# Power.net
KiCad netlist of a schematic drawn in Altium Designer
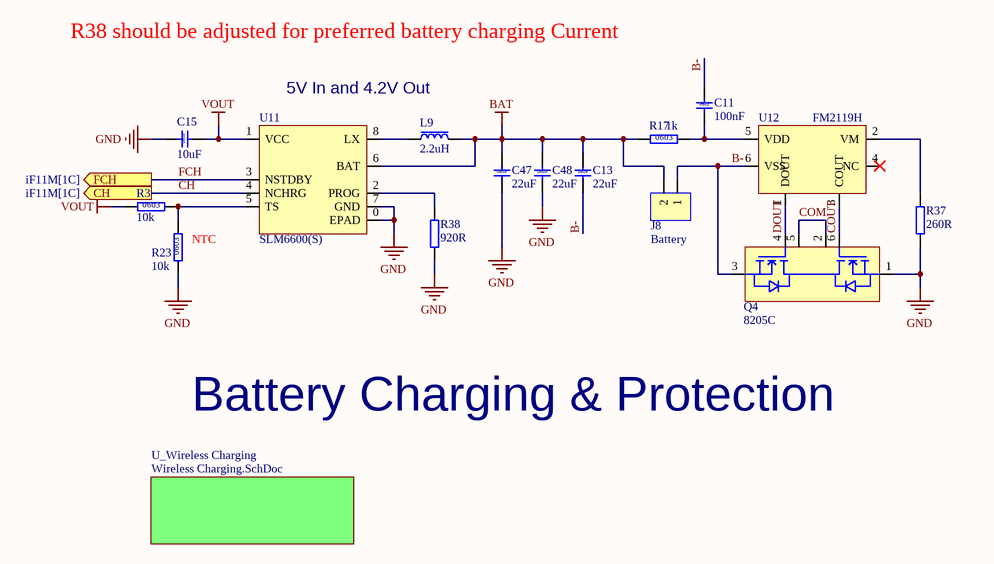
[diagram p0: Power.SchDoc]

(export (version "E")
  (design (tool "Eeschema 10.0.6"))
  (components
    (comp (ref "C11")
      (value "100nF")
      (footprint "C0603")
      (description "10% 50V")
      (fields (field (name "PART NO") "W-T-CA-X703N100K50VNT") (field (name "MANUFACTURER") "FENGHUA"))
      (libsource (lib "Rescap") (part "C 0603 100nF 50V"))
    )
    (comp (ref "C13")
      (value "22uF")
      (footprint "C0805")
      (description "10% 16V")
      (fields (field (name "PART NO") "WP0005367"))
      (libsource (lib "Rescap") (part "C 0805 22uF 16V"))
    )
    (comp (ref "C15")
      (value "10uF")
      (footprint "C0805")
      (description "10% 25V")
      (fields (field (name "PART NO") "WP0005368"))
      (libsource (lib "Rescap") (part "C 0805 10uF 25V"))
    )
    (comp (ref "C47")
      (value "22uF")
      (footprint "C0805")
      (description "10% 16V")
      (fields (field (name "PART NO") "WP0005367"))
      (libsource (lib "Rescap") (part "C 0805 22uF 16V"))
    )
    (comp (ref "C48")
      (value "22uF")
      (footprint "C0805")
      (description "10% 16V")
      (fields (field (name "PART NO") "WP0005367"))
      (libsource (lib "Rescap") (part "C 0805 22uF 16V"))
    )
    (comp (ref "J8")
      (value "Battery")
      (footprint "B2B-PH-2mm")
      (description "B2B PH 1X2 2 Pin B2B Connector")
      (libsource (lib "Connector") (part "B2B-PH-2MM"))
    )
    (comp (ref "L9")
      (value "2.2uH")
      (footprint "CD54")
      (description "SMD Inductor 2.2 uH CD54")
      (libsource (lib "Inductor") (part "CD54"))
    )
    (comp (ref "Q4")
      (value "8205C")
      (footprint "SOT23-6")
      (description "20V N-channel enhancement MOS field effect transistor")
      (libsource (lib "Transistor") (part "JST8205S"))
    )
    (comp (ref "R3")
      (value "10k")
      (footprint "R0603-LD")
      (description "5%")
      (fields (field (name "PART NO") "W-T-RE-RS03K103JT") (field (name "MANUFACTURER") "热敏D541V11增加1颗用量"))
      (libsource (lib "Rescap") (part "R 0603 10k"))
    )
    (comp (ref "R17")
      (value "1k")
      (footprint "R0603-LD")
      (description "5%")
      (fields (field (name "PART NO") "W-T-RE-RS03K102JT") (field (name "MANUFACTURER") "LAGEO"))
      (libsource (lib "Rescap") (part "R 0603 1k"))
    )
    (comp (ref "R23")
      (value "10k")
      (footprint "R0603-LD")
      (description "5%")
      (fields (field (name "PART NO") "W-T-RE-RS03K103JT") (field (name "MANUFACTURER") "热敏D541V11增加1颗用量"))
      (libsource (lib "Rescap") (part "R 0603 10k"))
    )
    (comp (ref "R37") (value "260R") (footprint "R0603") (libsource (lib "Resistor") (part "Resistor")))
    (comp (ref "R38") (value "920R") (footprint "R0603") (libsource (lib "Resistor") (part "Resistor")))
    (comp (ref "U11")
      (value "SLM6600(S)")
      (footprint "SOP-8 - EPAD")
      (libsource (lib "mylib2") (part "SLM6600(S)"))
    )
    (comp (ref "U12") (value "FM2119H") (footprint "SOT23-6") (libsource (lib "mylib2") (part "FM2119H")))
  )
  (nets
    (net (code "1") (name "/B-") (class "Default")
      (node (ref "C11") (pin "1") (pinfunction "1_1") (pintype "passive"))
      (node (ref "C13") (pin "2") (pinfunction "2_2") (pintype "passive"))
      (node (ref "J8") (pin "1") (pinfunction "1_1") (pintype "passive"))
      (node (ref "Q4") (pin "3") (pinfunction "S2_3") (pintype "passive"))
      (node (ref "U12") (pin "6") (pinfunction "VSS_6") (pintype "passive"))
    )
    (net (code "2") (name "/CH") (class "Default")
      (node (ref "U11") (pin "4") (pinfunction "NCHRG_4") (pintype "passive"))
    )
    (net (code "3") (name "/COM") (class "Default")
      (node (ref "Q4") (pin "2") (pinfunction "D1_2") (pintype "passive"))
      (node (ref "Q4") (pin "5") (pinfunction "D2_5") (pintype "passive"))
    )
    (net (code "4") (name "/COUT") (class "Default")
      (node (ref "Q4") (pin "6") (pinfunction "G1_6") (pintype "passive"))
      (node (ref "U12") (pin "3") (pinfunction "COUT_3") (pintype "passive"))
    )
    (net (code "5") (name "/DOUT") (class "Default")
      (node (ref "Q4") (pin "4") (pinfunction "G2_4") (pintype "passive"))
      (node (ref "U12") (pin "1") (pinfunction "DOUT_1") (pintype "passive"))
    )
    (net (code "6") (name "/FCH") (class "Default")
      (node (ref "U11") (pin "3") (pinfunction "NSTDBY_3") (pintype "passive"))
    )
    (net (code "7") (name "BAT") (class "Default")
      (node (ref "C13") (pin "1") (pinfunction "1_1") (pintype "passive"))
      (node (ref "C47") (pin "1") (pinfunction "1_1") (pintype "passive"))
      (node (ref "C48") (pin "1") (pinfunction "1_1") (pintype "passive"))
      (node (ref "J8") (pin "2") (pinfunction "2_2") (pintype "passive"))
      (node (ref "L9") (pin "2") (pinfunction "2_2") (pintype "passive"))
      (node (ref "R17") (pin "1") (pinfunction "1_1") (pintype "passive"))
      (node (ref "U11") (pin "6") (pinfunction "BAT_6") (pintype "passive"))
    )
    (net (code "8") (name "GND") (class "Default")
      (node (ref "C15") (pin "1") (pinfunction "1_1") (pintype "passive"))
      (node (ref "C47") (pin "2") (pinfunction "2_2") (pintype "passive"))
      (node (ref "C48") (pin "2") (pinfunction "2_2") (pintype "passive"))
      (node (ref "Q4") (pin "1") (pinfunction "S1_1") (pintype "passive"))
      (node (ref "R23") (pin "1") (pinfunction "1_1") (pintype "passive"))
      (node (ref "R37") (pin "1") (pinfunction "1_1") (pintype "passive"))
      (node (ref "R38") (pin "1") (pinfunction "1_1") (pintype "passive"))
      (node (ref "U11") (pin "0") (pinfunction "EPAD_0") (pintype "passive"))
      (node (ref "U11") (pin "7") (pinfunction "GND_7") (pintype "passive"))
    )
    (net (code "9") (name "Net-(Q4-D)") (class "Default")
      (node (ref "Q4") (pin "1") (pinfunction "D_1") (pintype "passive"))
    )
    (net (code "10") (name "Net-(U11-LX)") (class "Default")
      (node (ref "L9") (pin "1") (pinfunction "1_1") (pintype "passive"))
      (node (ref "U11") (pin "8") (pinfunction "LX_8") (pintype "passive"))
    )
    (net (code "11") (name "Net-(U11-PROG)") (class "Default")
      (node (ref "R38") (pin "2") (pinfunction "2_2") (pintype "passive"))
      (node (ref "U11") (pin "2") (pinfunction "PROG_2") (pintype "passive"))
    )
    (net (code "12") (name "Net-(U11-TS)") (class "Default")
      (node (ref "R23") (pin "2") (pinfunction "2_2") (pintype "passive"))
      (node (ref "R3") (pin "2") (pinfunction "2_2") (pintype "passive"))
      (node (ref "U11") (pin "5") (pinfunction "TS_5") (pintype "passive"))
    )
    (net (code "13") (name "Net-(U12-VDD)") (class "Default")
      (node (ref "C11") (pin "2") (pinfunction "2_2") (pintype "passive"))
      (node (ref "R17") (pin "2") (pinfunction "2_2") (pintype "passive"))
      (node (ref "U12") (pin "5") (pinfunction "VDD_5") (pintype "passive"))
    )
    (net (code "14") (name "Net-(U12-VM)") (class "Default")
      (node (ref "R37") (pin "2") (pinfunction "2_2") (pintype "passive"))
      (node (ref "U12") (pin "2") (pinfunction "VM_2") (pintype "passive"))
    )
    (net (code "15") (name "VOUT") (class "Default")
      (node (ref "C15") (pin "2") (pinfunction "2_2") (pintype "passive"))
      (node (ref "R3") (pin "1") (pinfunction "1_1") (pintype "passive"))
      (node (ref "U11") (pin "1") (pinfunction "VCC_1") (pintype "passive"))
    )
    (net (code "16") (name "unconnected-(U12-NC-Pad4)") (class "Default")
      (node (ref "U12") (pin "4") (pinfunction "NC_4") (pintype "passive+no_connect"))
    )
  )
)
